# MCU_Platform.net
KiCad netlist of a schematic drawn in Altium Designer
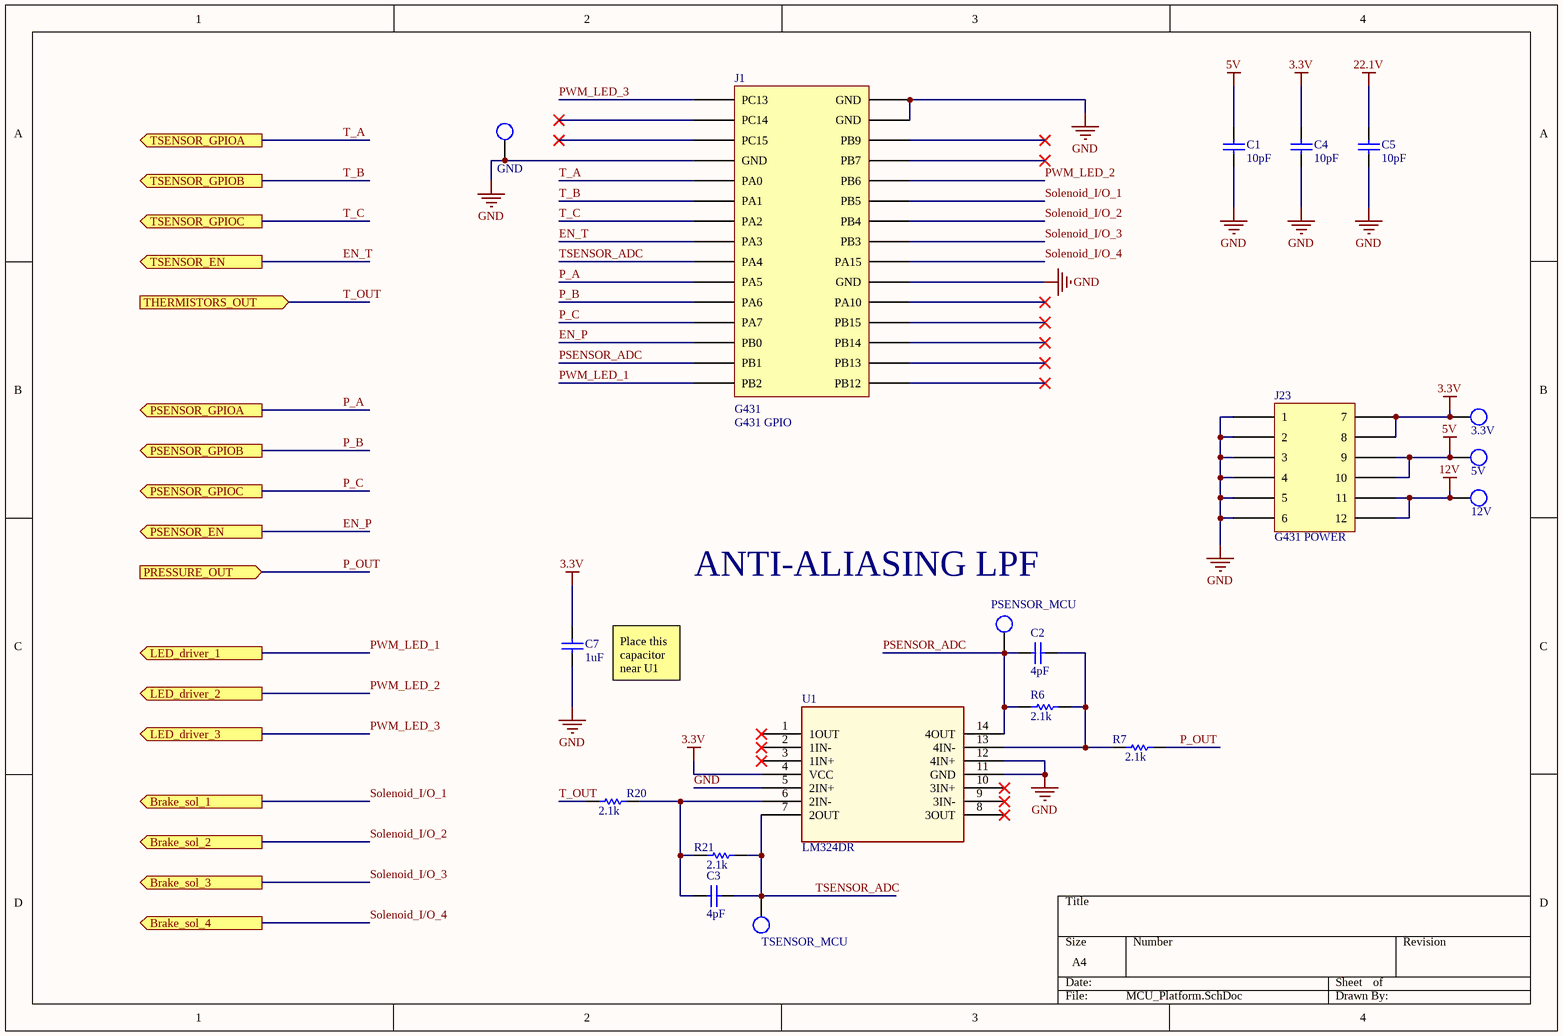
[diagram p0: MCU_Platform.SchDoc]

(export (version "E")
  (design (tool "Eeschema 10.0.6"))
  (components
    (comp (ref "3.3V")
      (value "Test Point")
      (footprint "Test Point - 5002")
      (libsource (lib "General") (part "Test Point"))
    )
    (comp (ref "5V")
      (value "Test Point")
      (footprint "Test Point - 5002")
      (libsource (lib "General") (part "Test Point"))
    )
    (comp (ref "12V")
      (value "Test Point")
      (footprint "Test Point - 5002")
      (libsource (lib "General") (part "Test Point"))
    )
    (comp (ref "C1")
      (value "10pF")
      (footprint "0603 - Capacitor")
      (description "Nonpolarized Capacitor")
      (fields (field (name "Comment") "Capacitor - Nonpolarized"))
      (libsource (lib "General") (part "Capacitor - Nonpolarized"))
    )
    (comp (ref "C2")
      (value "4pF")
      (footprint "0603 - Capacitor")
      (description "Nonpolarized Capacitor")
      (fields (field (name "Comment") "Capacitor - Nonpolarized"))
      (libsource (lib "General") (part "Capacitor - Nonpolarized"))
    )
    (comp (ref "C3")
      (value "4pF")
      (footprint "0603 - Capacitor")
      (description "Nonpolarized Capacitor")
      (fields (field (name "Comment") "Capacitor - Nonpolarized"))
      (libsource (lib "General") (part "Capacitor - Nonpolarized"))
    )
    (comp (ref "C4")
      (value "10pF")
      (footprint "0603 - Capacitor")
      (description "Nonpolarized Capacitor")
      (fields (field (name "Comment") "Capacitor - Nonpolarized"))
      (libsource (lib "General") (part "Capacitor - Nonpolarized"))
    )
    (comp (ref "C5")
      (value "10pF")
      (footprint "0603 - Capacitor")
      (description "Nonpolarized Capacitor")
      (fields (field (name "Comment") "Capacitor - Nonpolarized"))
      (libsource (lib "General") (part "Capacitor - Nonpolarized"))
    )
    (comp (ref "C7")
      (value "1uF")
      (footprint "0603 - Capacitor")
      (description "Nonpolarized Capacitor")
      (fields (field (name "Comment") "Capacitor - Nonpolarized"))
      (libsource (lib "General") (part "Capacitor - Nonpolarized"))
    )
    (comp (ref "GND")
      (value "Test Point")
      (footprint "Test Point - 5002")
      (libsource (lib "General") (part "Test Point"))
    )
    (comp (ref "J1")
      (value "G431 GPIO")
      (footprint "G431 Header (GPIO Connector)")
      (description "PPPC152LJBN-RC (30 Position Header Connector 0.100\" (2.54mm) Through Hole, Right Angle Gold)")
      (libsource (lib "MCUBoards") (part "G431 GPIO"))
    )
    (comp (ref "J23")
      (value "G431 POWER")
      (footprint "G431 HEADER (POWER CONNECTOR)")
      (description "PPPC062LJBN-RC (12 Position Header Connector 0.100\" (2.54mm) Through Hole, Right Angle Gold)")
      (fields (field (name "MANUFACTURER PART NUMBER") "PPPC062LJBN-RC"))
      (libsource (lib "MCUBoards") (part "G431 POWER"))
    )
    (comp (ref "PSENSOR_MCU")
      (value "Test Point")
      (footprint "Test Point - 5002")
      (libsource (lib "General") (part "Test Point"))
    )
    (comp (ref "R6")
      (value "2.1k")
      (footprint "0805 - Resistor")
      (description "Resistor")
      (libsource (lib "General") (part "Resistor"))
    )
    (comp (ref "R7")
      (value "2.1k")
      (footprint "0805 - Resistor")
      (description "Resistor")
      (libsource (lib "General") (part "Resistor"))
    )
    (comp (ref "R20")
      (value "2.1k")
      (footprint "0805 - Resistor")
      (description "Resistor")
      (libsource (lib "General") (part "Resistor"))
    )
    (comp (ref "R21")
      (value "2.1k")
      (footprint "0805 - Resistor")
      (description "Resistor")
      (libsource (lib "General") (part "Resistor"))
    )
    (comp (ref "TSENSOR_MCU")
      (value "Test Point")
      (footprint "Test Point - 5002")
      (libsource (lib "General") (part "Test Point"))
    )
    (comp (ref "U1")
      (value "LM324DR")
      (footprint "LM324DR")
      (description "General Purpose Amplifier 4 Circuit 14-SOIC")
      (libsource (lib "GeneralComponents") (part "LM324DR"))
    )
  )
  (nets
    (net (code "1") (name "/EN_P") (class "Default")
      (node (ref "J1") (pin "13") (pinfunction "PB0_13") (pintype "passive"))
    )
    (net (code "2") (name "/EN_T") (class "Default")
      (node (ref "J1") (pin "8") (pinfunction "PA3_8") (pintype "passive"))
    )
    (net (code "3") (name "/PSENSOR_ADC") (class "Default")
      (node (ref "C2") (pin "1") (pinfunction "1_1") (pintype "passive"))
      (node (ref "J1") (pin "14") (pinfunction "PB1_14") (pintype "passive"))
      (node (ref "PSENSOR_MCU") (pin "1") (pinfunction "0_1") (pintype "passive"))
      (node (ref "R6") (pin "1") (pinfunction "1_1") (pintype "passive"))
      (node (ref "U1") (pin "14") (pinfunction "4OUT_14") (pintype "passive"))
    )
    (net (code "4") (name "/PWM_LED_1") (class "Default")
      (node (ref "J1") (pin "15") (pinfunction "PB2_15") (pintype "passive"))
    )
    (net (code "5") (name "/PWM_LED_2") (class "Default")
      (node (ref "J1") (pin "20") (pinfunction "PB6_20") (pintype "passive"))
    )
    (net (code "6") (name "/PWM_LED_3") (class "Default")
      (node (ref "J1") (pin "1") (pinfunction "PC13_1") (pintype "passive"))
    )
    (net (code "7") (name "/P_A") (class "Default")
      (node (ref "J1") (pin "10") (pinfunction "PA5_10") (pintype "passive"))
    )
    (net (code "8") (name "/P_B") (class "Default")
      (node (ref "J1") (pin "11") (pinfunction "PA6_11") (pintype "passive"))
    )
    (net (code "9") (name "/P_C") (class "Default")
      (node (ref "J1") (pin "12") (pinfunction "PA7_12") (pintype "passive"))
    )
    (net (code "10") (name "/P_OUT") (class "Default")
      (node (ref "R7") (pin "2") (pinfunction "2_2") (pintype "passive"))
    )
    (net (code "11") (name "/Solenoid_I{slash}O_1") (class "Default")
      (node (ref "J1") (pin "21") (pinfunction "PB5_21") (pintype "passive"))
    )
    (net (code "12") (name "/Solenoid_I{slash}O_2") (class "Default")
      (node (ref "J1") (pin "22") (pinfunction "PB4_22") (pintype "passive"))
    )
    (net (code "13") (name "/Solenoid_I{slash}O_3") (class "Default")
      (node (ref "J1") (pin "23") (pinfunction "PB3_23") (pintype "passive"))
    )
    (net (code "14") (name "/Solenoid_I{slash}O_4") (class "Default")
      (node (ref "J1") (pin "24") (pinfunction "PA15_24") (pintype "passive"))
    )
    (net (code "15") (name "/TSENSOR_ADC") (class "Default")
      (node (ref "C3") (pin "1") (pinfunction "1_1") (pintype "passive"))
      (node (ref "J1") (pin "9") (pinfunction "PA4_9") (pintype "passive"))
      (node (ref "R21") (pin "2") (pinfunction "2_2") (pintype "passive"))
      (node (ref "TSENSOR_MCU") (pin "1") (pinfunction "0_1") (pintype "passive"))
      (node (ref "U1") (pin "7") (pinfunction "2OUT_7") (pintype "passive"))
    )
    (net (code "16") (name "/T_A") (class "Default")
      (node (ref "J1") (pin "5") (pinfunction "PA0_5") (pintype "passive"))
    )
    (net (code "17") (name "/T_B") (class "Default")
      (node (ref "J1") (pin "6") (pinfunction "PA1_6") (pintype "passive"))
    )
    (net (code "18") (name "/T_C") (class "Default")
      (node (ref "J1") (pin "7") (pinfunction "PA2_7") (pintype "passive"))
    )
    (net (code "19") (name "/T_OUT") (class "Default")
      (node (ref "R20") (pin "1") (pinfunction "1_1") (pintype "passive"))
    )
    (net (code "20") (name "3.3V") (class "Default")
      (node (ref "3.3V") (pin "1") (pinfunction "0_1") (pintype "passive"))
      (node (ref "C4") (pin "2") (pinfunction "2_2") (pintype "passive"))
      (node (ref "C7") (pin "2") (pinfunction "2_2") (pintype "passive"))
      (node (ref "J23") (pin "7") (pinfunction "7_7") (pintype "passive"))
      (node (ref "J23") (pin "8") (pinfunction "8_8") (pintype "passive"))
      (node (ref "U1") (pin "4") (pinfunction "VCC_4") (pintype "power_in"))
    )
    (net (code "21") (name "5V") (class "Default")
      (node (ref "5V") (pin "1") (pinfunction "0_1") (pintype "passive"))
      (node (ref "C1") (pin "2") (pinfunction "2_2") (pintype "passive"))
      (node (ref "J23") (pin "10") (pinfunction "10_10") (pintype "passive"))
      (node (ref "J23") (pin "9") (pinfunction "9_9") (pintype "passive"))
    )
    (net (code "22") (name "12V") (class "Default")
      (node (ref "12V") (pin "1") (pinfunction "0_1") (pintype "passive"))
      (node (ref "J23") (pin "11") (pinfunction "11_11") (pintype "passive"))
      (node (ref "J23") (pin "12") (pinfunction "12_12") (pintype "passive"))
    )
    (net (code "23") (name "22.1V") (class "Default")
      (node (ref "C5") (pin "2") (pinfunction "2_2") (pintype "passive"))
    )
    (net (code "24") (name "GND") (class "Default")
      (node (ref "C1") (pin "1") (pinfunction "1_1") (pintype "passive"))
      (node (ref "C4") (pin "1") (pinfunction "1_1") (pintype "passive"))
      (node (ref "C5") (pin "1") (pinfunction "1_1") (pintype "passive"))
      (node (ref "C7") (pin "1") (pinfunction "1_1") (pintype "passive"))
      (node (ref "GND") (pin "1") (pinfunction "0_1") (pintype "passive"))
      (node (ref "J1") (pin "16") (pinfunction "GND_16") (pintype "passive"))
      (node (ref "J1") (pin "17") (pinfunction "GND_17") (pintype "passive"))
      (node (ref "J1") (pin "25") (pinfunction "GND_25") (pintype "passive"))
      (node (ref "J1") (pin "4") (pinfunction "GND_4") (pintype "passive"))
      (node (ref "J23") (pin "1") (pinfunction "1_1") (pintype "passive"))
      (node (ref "J23") (pin "2") (pinfunction "2_2") (pintype "passive"))
      (node (ref "J23") (pin "3") (pinfunction "3_3") (pintype "passive"))
      (node (ref "J23") (pin "4") (pinfunction "4_4") (pintype "passive"))
      (node (ref "J23") (pin "5") (pinfunction "5_5") (pintype "passive"))
      (node (ref "J23") (pin "6") (pinfunction "6_6") (pintype "passive"))
      (node (ref "U1") (pin "11") (pinfunction "GND_11") (pintype "power_in"))
      (node (ref "U1") (pin "12") (pinfunction "4IN+_12") (pintype "passive"))
      (node (ref "U1") (pin "5") (pinfunction "2IN+_5") (pintype "passive"))
    )
    (net (code "25") (name "Net-(U1-2IN-)") (class "Default")
      (node (ref "C3") (pin "2") (pinfunction "2_2") (pintype "passive"))
      (node (ref "R20") (pin "2") (pinfunction "2_2") (pintype "passive"))
      (node (ref "R21") (pin "1") (pinfunction "1_1") (pintype "passive"))
      (node (ref "U1") (pin "6") (pinfunction "2IN-_6") (pintype "passive"))
    )
    (net (code "26") (name "Net-(U1-4IN-)") (class "Default")
      (node (ref "C2") (pin "2") (pinfunction "2_2") (pintype "passive"))
      (node (ref "R6") (pin "2") (pinfunction "2_2") (pintype "passive"))
      (node (ref "R7") (pin "1") (pinfunction "1_1") (pintype "passive"))
      (node (ref "U1") (pin "13") (pinfunction "4IN-_13") (pintype "passive"))
    )
    (net (code "27") (name "unconnected-(J1-PA10-Pad26)") (class "Default")
      (node (ref "J1") (pin "26") (pinfunction "PA10_26") (pintype "passive+no_connect"))
    )
    (net (code "28") (name "unconnected-(J1-PB7-Pad19)") (class "Default")
      (node (ref "J1") (pin "19") (pinfunction "PB7_19") (pintype "passive+no_connect"))
    )
    (net (code "29") (name "unconnected-(J1-PB9-Pad18)") (class "Default")
      (node (ref "J1") (pin "18") (pinfunction "PB9_18") (pintype "passive+no_connect"))
    )
    (net (code "30") (name "unconnected-(J1-PB12-Pad30)") (class "Default")
      (node (ref "J1") (pin "30") (pinfunction "PB12_30") (pintype "passive+no_connect"))
    )
    (net (code "31") (name "unconnected-(J1-PB13-Pad29)") (class "Default")
      (node (ref "J1") (pin "29") (pinfunction "PB13_29") (pintype "passive+no_connect"))
    )
    (net (code "32") (name "unconnected-(J1-PB14-Pad28)") (class "Default")
      (node (ref "J1") (pin "28") (pinfunction "PB14_28") (pintype "passive+no_connect"))
    )
    (net (code "33") (name "unconnected-(J1-PB15-Pad27)") (class "Default")
      (node (ref "J1") (pin "27") (pinfunction "PB15_27") (pintype "passive+no_connect"))
    )
    (net (code "34") (name "unconnected-(J1-PC14-Pad2)") (class "Default")
      (node (ref "J1") (pin "2") (pinfunction "PC14_2") (pintype "passive+no_connect"))
    )
    (net (code "35") (name "unconnected-(J1-PC15-Pad3)") (class "Default")
      (node (ref "J1") (pin "3") (pinfunction "PC15_3") (pintype "passive+no_connect"))
    )
    (net (code "36") (name "unconnected-(U1-1IN+-Pad3)") (class "Default")
      (node (ref "U1") (pin "3") (pinfunction "1IN+_3") (pintype "passive+no_connect"))
    )
    (net (code "37") (name "unconnected-(U1-1IN--Pad2)") (class "Default")
      (node (ref "U1") (pin "2") (pinfunction "1IN-_2") (pintype "passive+no_connect"))
    )
    (net (code "38") (name "unconnected-(U1-1OUT-Pad1)") (class "Default")
      (node (ref "U1") (pin "1") (pinfunction "1OUT_1") (pintype "passive+no_connect"))
    )
    (net (code "39") (name "unconnected-(U1-3IN+-Pad10)") (class "Default")
      (node (ref "U1") (pin "10") (pinfunction "3IN+_10") (pintype "passive+no_connect"))
    )
    (net (code "40") (name "unconnected-(U1-3IN--Pad9)") (class "Default")
      (node (ref "U1") (pin "9") (pinfunction "3IN-_9") (pintype "passive+no_connect"))
    )
    (net (code "41") (name "unconnected-(U1-3OUT-Pad8)") (class "Default")
      (node (ref "U1") (pin "8") (pinfunction "3OUT_8") (pintype "passive+no_connect"))
    )
  )
)
